# GateWay.net
KiCad netlist of a schematic drawn in Altium Designer
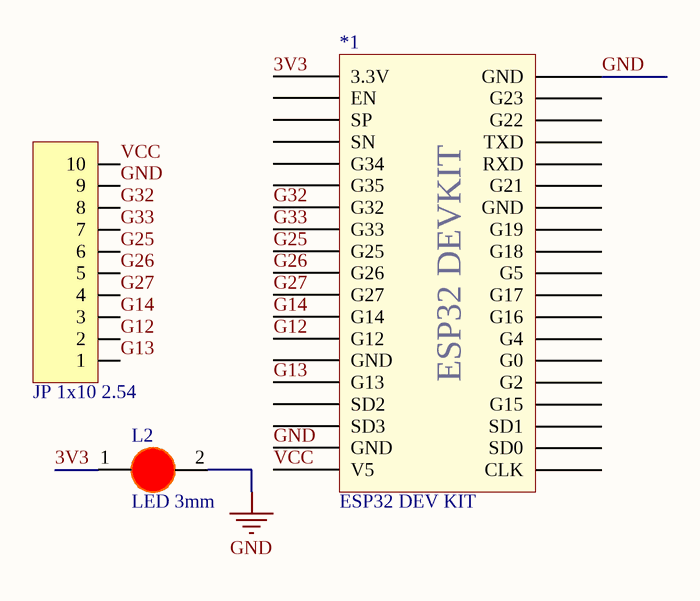
[diagram p0: GateWay.SchDoc]

(export (version "E")
  (design (tool "Eeschema 10.0.6"))
  (components
    (comp (ref "*1")
      (value "ESP32 DEV KIT")
      (footprint "ESP32 DEVKIT")
      (libsource (lib "Altium_Lib_by_KhueNguyenCreator") (part "ESP32 DEV KIT"))
    )
    (comp (ref "JP5")
      (value "JP 1x10 2.54")
      (footprint "JP 1x10 CT")
      (description "Cắm")
      (libsource (lib "OCVITTV") (part "JP 1x10 2.54 Cai Thang"))
    )
    (comp (ref "L2")
      (value "LED 3mm")
      (footprint "LED-3MM-RED")
      (description "Cắm")
      (libsource (lib "OCVITTV") (part "LED 3mm Do"))
    )
  )
  (nets
    (net (code "1") (name "/3V3") (class "Default")
      (node (ref "*1") (pin "1") (pinfunction "3.3V_1") (pintype "passive"))
      (node (ref "L2") (pin "1") (pinfunction "A_1") (pintype "passive"))
    )
    (net (code "2") (name "/G12") (class "Default")
      (node (ref "*1") (pin "13") (pinfunction "G12_13") (pintype "passive"))
      (node (ref "JP5") (pin "2") (pinfunction "2_2") (pintype "passive"))
    )
    (net (code "3") (name "/G13") (class "Default")
      (node (ref "*1") (pin "15") (pinfunction "G13_15") (pintype "passive"))
      (node (ref "JP5") (pin "1") (pinfunction "1_1") (pintype "passive"))
    )
    (net (code "4") (name "/G14") (class "Default")
      (node (ref "*1") (pin "12") (pinfunction "G14_12") (pintype "passive"))
      (node (ref "JP5") (pin "3") (pinfunction "3_3") (pintype "passive"))
    )
    (net (code "5") (name "/G25") (class "Default")
      (node (ref "*1") (pin "9") (pinfunction "G25_9") (pintype "passive"))
      (node (ref "JP5") (pin "6") (pinfunction "6_6") (pintype "passive"))
    )
    (net (code "6") (name "/G26") (class "Default")
      (node (ref "*1") (pin "10") (pinfunction "G26_10") (pintype "passive"))
      (node (ref "JP5") (pin "5") (pinfunction "5_5") (pintype "passive"))
    )
    (net (code "7") (name "/G27") (class "Default")
      (node (ref "*1") (pin "11") (pinfunction "G27_11") (pintype "passive"))
      (node (ref "JP5") (pin "4") (pinfunction "4_4") (pintype "passive"))
    )
    (net (code "8") (name "/G32") (class "Default")
      (node (ref "*1") (pin "7") (pinfunction "G32_7") (pintype "passive"))
      (node (ref "JP5") (pin "8") (pinfunction "8_8") (pintype "passive"))
    )
    (net (code "9") (name "/G33") (class "Default")
      (node (ref "*1") (pin "8") (pinfunction "G33_8") (pintype "passive"))
      (node (ref "JP5") (pin "7") (pinfunction "7_7") (pintype "passive"))
    )
    (net (code "10") (name "/VCC") (class "Default")
      (node (ref "*1") (pin "19") (pinfunction "V5_19") (pintype "passive"))
      (node (ref "JP5") (pin "10") (pinfunction "10_10") (pintype "passive"))
    )
    (net (code "11") (name "GND") (class "Default")
      (node (ref "*1") (pin "18") (pinfunction "GND_18") (pintype "passive"))
      (node (ref "*1") (pin "38") (pinfunction "GND_38") (pintype "passive"))
      (node (ref "JP5") (pin "9") (pinfunction "9_9") (pintype "passive"))
      (node (ref "L2") (pin "2") (pinfunction "K_2") (pintype "passive"))
    )
    (net (code "12") (name "unconnected-(*1-CLK-Pad20)") (class "Default")
      (node (ref "*1") (pin "20") (pinfunction "CLK_20") (pintype "passive"))
    )
    (net (code "13") (name "unconnected-(*1-EN-Pad2)") (class "Default")
      (node (ref "*1") (pin "2") (pinfunction "EN_2") (pintype "passive"))
    )
    (net (code "14") (name "unconnected-(*1-G0-Pad25)") (class "Default")
      (node (ref "*1") (pin "25") (pinfunction "G0_25") (pintype "passive"))
    )
    (net (code "15") (name "unconnected-(*1-G2-Pad24)") (class "Default")
      (node (ref "*1") (pin "24") (pinfunction "G2_24") (pintype "passive"))
    )
    (net (code "16") (name "unconnected-(*1-G4-Pad26)") (class "Default")
      (node (ref "*1") (pin "26") (pinfunction "G4_26") (pintype "passive"))
    )
    (net (code "17") (name "unconnected-(*1-G5-Pad29)") (class "Default")
      (node (ref "*1") (pin "29") (pinfunction "G5_29") (pintype "passive"))
    )
    (net (code "18") (name "unconnected-(*1-G15-Pad23)") (class "Default")
      (node (ref "*1") (pin "23") (pinfunction "G15_23") (pintype "passive"))
    )
    (net (code "19") (name "unconnected-(*1-G16-Pad27)") (class "Default")
      (node (ref "*1") (pin "27") (pinfunction "G16_27") (pintype "passive"))
    )
    (net (code "20") (name "unconnected-(*1-G17-Pad28)") (class "Default")
      (node (ref "*1") (pin "28") (pinfunction "G17_28") (pintype "passive"))
    )
    (net (code "21") (name "unconnected-(*1-G18-Pad30)") (class "Default")
      (node (ref "*1") (pin "30") (pinfunction "G18_30") (pintype "passive"))
    )
    (net (code "22") (name "unconnected-(*1-G19-Pad31)") (class "Default")
      (node (ref "*1") (pin "31") (pinfunction "G19_31") (pintype "passive"))
    )
    (net (code "23") (name "unconnected-(*1-G21-Pad33)") (class "Default")
      (node (ref "*1") (pin "33") (pinfunction "G21_33") (pintype "passive"))
    )
    (net (code "24") (name "unconnected-(*1-G22-Pad36)") (class "Default")
      (node (ref "*1") (pin "36") (pinfunction "G22_36") (pintype "passive"))
    )
    (net (code "25") (name "unconnected-(*1-G23-Pad37)") (class "Default")
      (node (ref "*1") (pin "37") (pinfunction "G23_37") (pintype "passive"))
    )
    (net (code "26") (name "unconnected-(*1-G34-Pad5)") (class "Default")
      (node (ref "*1") (pin "5") (pinfunction "G34_5") (pintype "passive"))
    )
    (net (code "27") (name "unconnected-(*1-G35-Pad6)") (class "Default")
      (node (ref "*1") (pin "6") (pinfunction "G35_6") (pintype "passive"))
    )
    (net (code "28") (name "unconnected-(*1-GND-Pad14)") (class "Default")
      (node (ref "*1") (pin "14") (pinfunction "GND_14") (pintype "passive"))
    )
    (net (code "29") (name "unconnected-(*1-GND-Pad32)") (class "Default")
      (node (ref "*1") (pin "32") (pinfunction "GND_32") (pintype "passive"))
    )
    (net (code "30") (name "unconnected-(*1-RXD-Pad34)") (class "Default")
      (node (ref "*1") (pin "34") (pinfunction "RXD_34") (pintype "passive"))
    )
    (net (code "31") (name "unconnected-(*1-SD0-Pad21)") (class "Default")
      (node (ref "*1") (pin "21") (pinfunction "SD0_21") (pintype "passive"))
    )
    (net (code "32") (name "unconnected-(*1-SD1-Pad22)") (class "Default")
      (node (ref "*1") (pin "22") (pinfunction "SD1_22") (pintype "passive"))
    )
    (net (code "33") (name "unconnected-(*1-SD2-Pad16)") (class "Default")
      (node (ref "*1") (pin "16") (pinfunction "SD2_16") (pintype "passive"))
    )
    (net (code "34") (name "unconnected-(*1-SD3-Pad17)") (class "Default")
      (node (ref "*1") (pin "17") (pinfunction "SD3_17") (pintype "passive"))
    )
    (net (code "35") (name "unconnected-(*1-SN-Pad4)") (class "Default")
      (node (ref "*1") (pin "4") (pinfunction "SN_4") (pintype "passive"))
    )
    (net (code "36") (name "unconnected-(*1-SP-Pad3)") (class "Default")
      (node (ref "*1") (pin "3") (pinfunction "SP_3") (pintype "passive"))
    )
    (net (code "37") (name "unconnected-(*1-TXD-Pad35)") (class "Default")
      (node (ref "*1") (pin "35") (pinfunction "TXD_35") (pintype "passive"))
    )
  )
)
